# Retro_Lite_CM5_Left_PCB_v1_-_RP2040.net
KiCad netlist of a schematic drawn in EAGLE
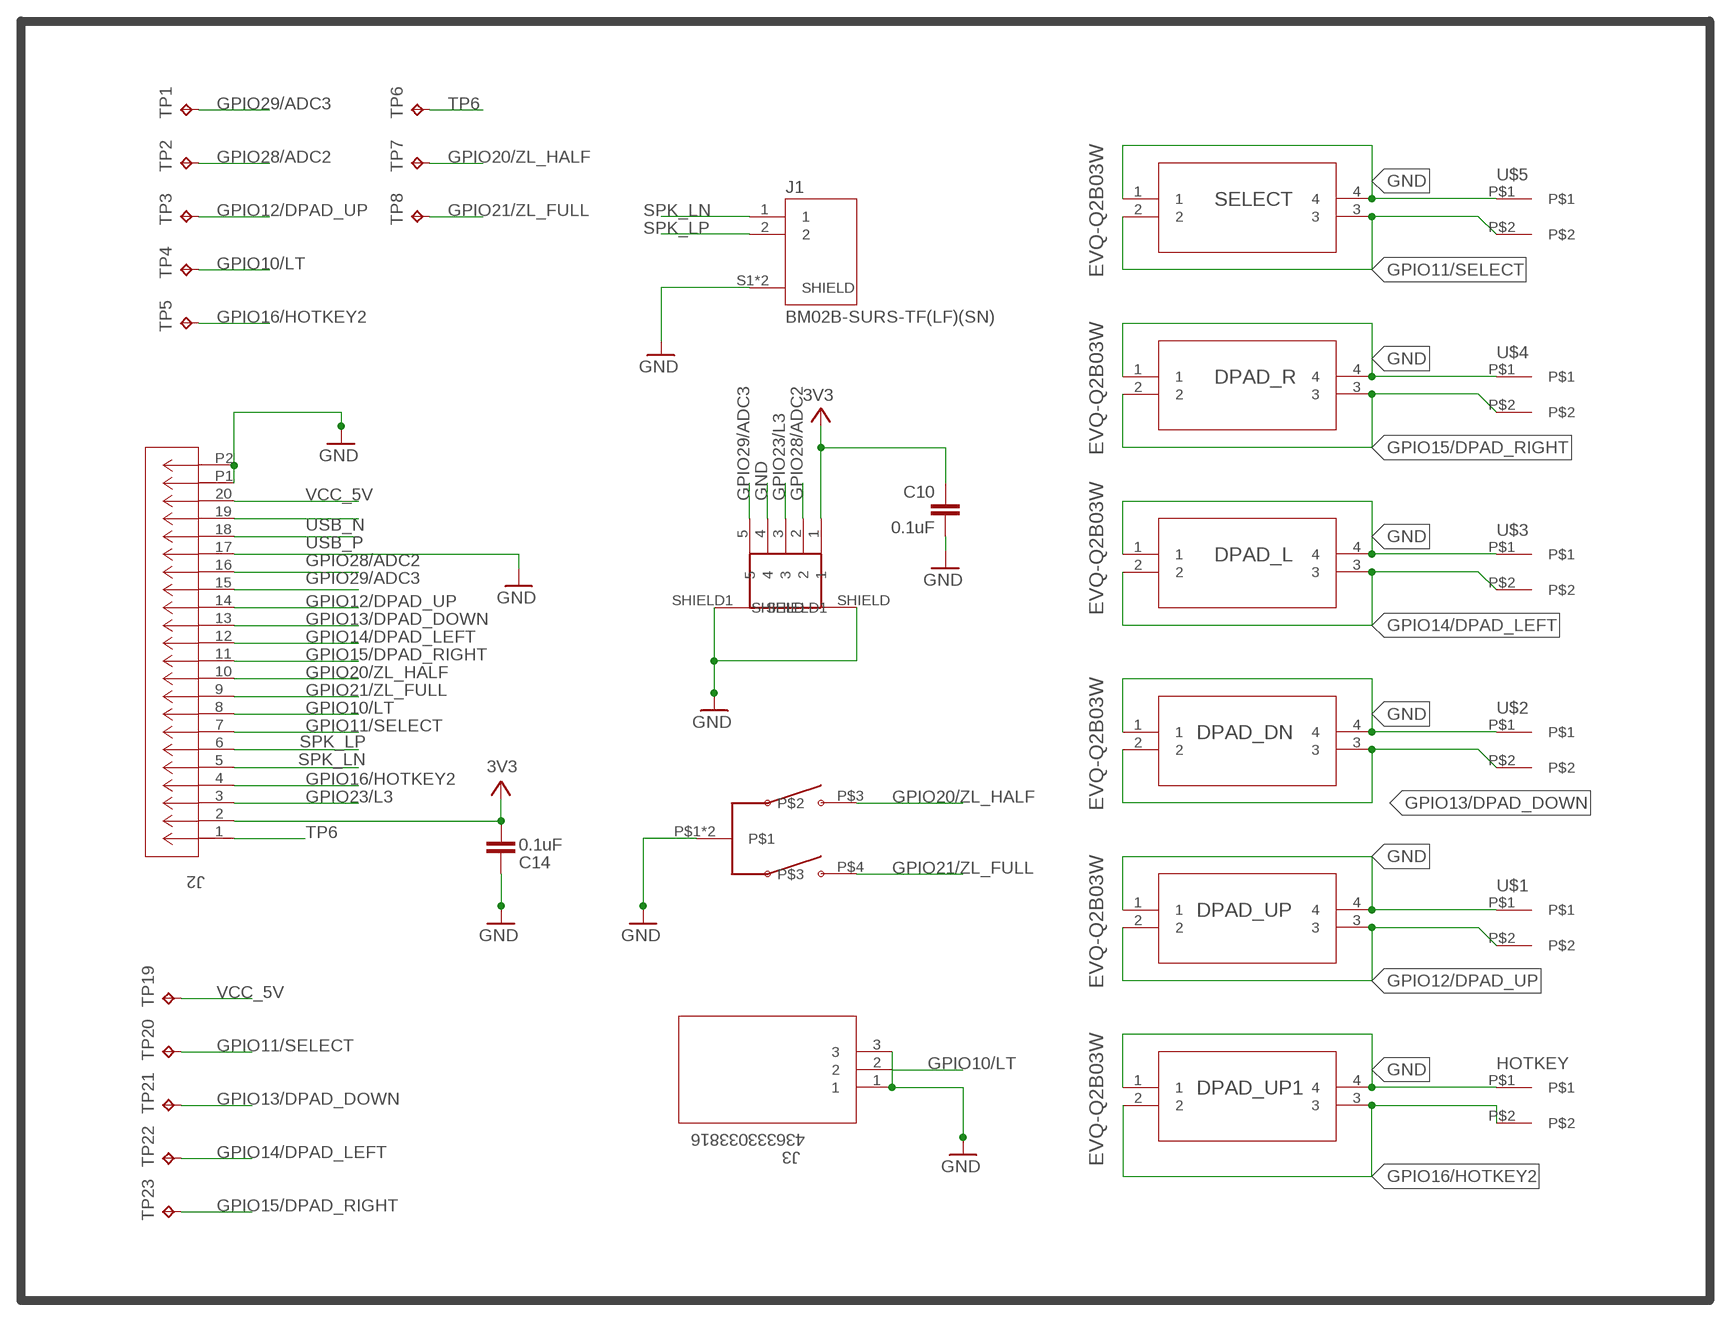
[diagram p0: schematic, sheet 1]

(export (version "E")
  (design (tool "Eeschema 10.0.6"))
  (components
    (comp (ref "C10")
      (value "0.1uF")
      (footprint "eagle-import:C0402")
      (libsource (lib "eagle-import") (part "C-EUC0402-YVELTAL"))
    )
    (comp (ref "C14")
      (value "0.1uF")
      (footprint "eagle-import:C0402")
      (libsource (lib "eagle-import") (part "C-EUC0402-YVELTAL"))
    )
    (comp (ref "DPAD_DN")
      (value "EVQ-Q2B03W")
      (footprint "eagle-import:EVQQ2_3")
      (fields (field (name "MF") "Panasonic Electronic") (field (name "MP") "EVQQ2B03W"))
      (libsource (lib "eagle-import") (part "EVQ-Q2B03W"))
    )
    (comp (ref "DPAD_L")
      (value "EVQ-Q2B03W")
      (footprint "eagle-import:EVQQ2_3")
      (fields (field (name "MF") "Panasonic Electronic") (field (name "MP") "EVQQ2B03W"))
      (libsource (lib "eagle-import") (part "EVQ-Q2B03W"))
    )
    (comp (ref "DPAD_R")
      (value "EVQ-Q2B03W")
      (footprint "eagle-import:EVQQ2_3")
      (fields (field (name "MF") "Panasonic Electronic") (field (name "MP") "EVQQ2B03W"))
      (libsource (lib "eagle-import") (part "EVQ-Q2B03W"))
    )
    (comp (ref "DPAD_UP")
      (value "EVQ-Q2B03W")
      (footprint "eagle-import:EVQQ2_3")
      (fields (field (name "MF") "Panasonic Electronic") (field (name "MP") "EVQQ2B03W"))
      (libsource (lib "eagle-import") (part "EVQ-Q2B03W"))
    )
    (comp (ref "DPAD_UP1")
      (value "EVQ-Q2B03W")
      (footprint "eagle-import:EVQQ2_3")
      (fields (field (name "MF") "Panasonic Electronic") (field (name "MP") "EVQQ2B03W"))
      (libsource (lib "eagle-import") (part "EVQ-Q2B03W"))
    )
    (comp (ref "HOTKEY")
      (value "MEMBRANEBUTTON")
      (footprint "eagle-import:MEMBRANEBUTTON")
      (libsource (lib "eagle-import") (part "MEMBRANEBUTTON"))
    )
    (comp (ref "J1")
      (value "BM02B-SURS-TF(LF)(SN)")
      (footprint "eagle-import:JST_BM02B-SURS-TF(LF)(SN)")
      (fields (field (name "MF") "JST Sales"))
      (libsource (lib "eagle-import") (part "BM02B-SURS-TF(LF)(SN)"))
    )
    (comp (ref "J2")
      (value "5034802000")
      (footprint "eagle-import:CON_5034802000_MOL")
      (fields (field (name "COPYRIGHT") "Copyright (C) 2023 Ultra Librarian. All rights reserved."))
      (libsource (lib "eagle-import") (part "5034802000"))
    )
    (comp (ref "J3")
      (value "436333033816")
      (footprint "eagle-import:CONN3_3033816_WRE")
      (fields (field (name "COPYRIGHT") "Copyright (C) 2023 Ultra Librarian. All rights reserved."))
      (libsource (lib "eagle-import") (part "436333033816"))
    )
    (comp (ref "SELECT")
      (value "EVQ-Q2B03W")
      (footprint "eagle-import:EVQQ2_3")
      (fields (field (name "MF") "Panasonic Electronic") (field (name "MP") "EVQQ2B03W"))
      (libsource (lib "eagle-import") (part "EVQ-Q2B03W"))
    )
    (comp (ref "TP1")
      (value "TPTP07R")
      (footprint "eagle-import:TP07R")
      (libsource (lib "eagle-import") (part "TPTP07R"))
    )
    (comp (ref "TP2")
      (value "TPTP07R")
      (footprint "eagle-import:TP07R")
      (libsource (lib "eagle-import") (part "TPTP07R"))
    )
    (comp (ref "TP3")
      (value "TPTP07R")
      (footprint "eagle-import:TP07R")
      (libsource (lib "eagle-import") (part "TPTP07R"))
    )
    (comp (ref "TP4")
      (value "TPTP07R")
      (footprint "eagle-import:TP07R")
      (libsource (lib "eagle-import") (part "TPTP07R"))
    )
    (comp (ref "TP5")
      (value "TPTP07R")
      (footprint "eagle-import:TP07R")
      (libsource (lib "eagle-import") (part "TPTP07R"))
    )
    (comp (ref "TP6")
      (value "TPTP07R")
      (footprint "eagle-import:TP07R")
      (libsource (lib "eagle-import") (part "TPTP07R"))
    )
    (comp (ref "TP7")
      (value "TPTP07R")
      (footprint "eagle-import:TP07R")
      (libsource (lib "eagle-import") (part "TPTP07R"))
    )
    (comp (ref "TP8")
      (value "TPTP07R")
      (footprint "eagle-import:TP07R")
      (libsource (lib "eagle-import") (part "TPTP07R"))
    )
    (comp (ref "TP19")
      (value "TPTP07R")
      (footprint "eagle-import:TP07R")
      (libsource (lib "eagle-import") (part "TPTP07R"))
    )
    (comp (ref "TP20")
      (value "TPTP07R")
      (footprint "eagle-import:TP07R")
      (libsource (lib "eagle-import") (part "TPTP07R"))
    )
    (comp (ref "TP21")
      (value "TPTP07R")
      (footprint "eagle-import:TP07R")
      (libsource (lib "eagle-import") (part "TPTP07R"))
    )
    (comp (ref "TP22")
      (value "TPTP07R")
      (footprint "eagle-import:TP07R")
      (libsource (lib "eagle-import") (part "TPTP07R"))
    )
    (comp (ref "TP23")
      (value "TPTP07R")
      (footprint "eagle-import:TP07R")
      (libsource (lib "eagle-import") (part "TPTP07R"))
    )
    (comp (ref "U$1")
      (value "MEMBRANEBUTTON")
      (footprint "eagle-import:MEMBRANEBUTTON")
      (libsource (lib "eagle-import") (part "MEMBRANEBUTTON"))
    )
    (comp (ref "U$2")
      (value "MEMBRANEBUTTON")
      (footprint "eagle-import:MEMBRANEBUTTON")
      (libsource (lib "eagle-import") (part "MEMBRANEBUTTON"))
    )
    (comp (ref "U$3")
      (value "MEMBRANEBUTTON")
      (footprint "eagle-import:MEMBRANEBUTTON")
      (libsource (lib "eagle-import") (part "MEMBRANEBUTTON"))
    )
    (comp (ref "U$4")
      (value "MEMBRANEBUTTON")
      (footprint "eagle-import:MEMBRANEBUTTON")
      (libsource (lib "eagle-import") (part "MEMBRANEBUTTON"))
    )
    (comp (ref "U$5")
      (value "MEMBRANEBUTTON")
      (footprint "eagle-import:MEMBRANEBUTTON")
      (libsource (lib "eagle-import") (part "MEMBRANEBUTTON"))
    )
    (comp (ref "U$7")
      (value "SWITCHSTICK_BREAKOUT")
      (footprint "eagle-import:SWITCHSTICK_BREAKOUT")
      (libsource (lib "eagle-import") (part "SWITCHSTICK_BREAKOUT"))
    )
    (comp (ref "U$8")
      (value "TMHF07")
      (footprint "eagle-import:TMHF07")
      (libsource (lib "eagle-import") (part "TMHF07"))
    )
  )
  (nets
    (net (code "1") (name "/GPIO10{slash}LT") (class "Default")
      (node (ref "J2") (pin "8") (pinfunction "8_8") (pintype "passive"))
      (node (ref "J3") (pin "2") (pinfunction "2_2") (pintype "passive"))
      (node (ref "TP4") (pin "TP") (pinfunction "TP_TP") (pintype "input"))
    )
    (net (code "2") (name "/GPIO20{slash}ZL_HALF") (class "Default")
      (node (ref "J2") (pin "10") (pinfunction "10_10") (pintype "passive"))
      (node (ref "TP7") (pin "TP") (pinfunction "TP_TP") (pintype "input"))
      (node (ref "U$8") (pin "P$3") (pinfunction "P$2_P$3") (pintype "bidirectional"))
    )
    (net (code "3") (name "/GPIO21{slash}ZL_FULL") (class "Default")
      (node (ref "J2") (pin "9") (pinfunction "9_9") (pintype "passive"))
      (node (ref "TP8") (pin "TP") (pinfunction "TP_TP") (pintype "input"))
      (node (ref "U$8") (pin "P$4") (pinfunction "P$3_P$4") (pintype "bidirectional"))
    )
    (net (code "4") (name "/GPIO23{slash}L3") (class "Default")
      (node (ref "J2") (pin "3") (pinfunction "3_3") (pintype "passive"))
      (node (ref "U$7") (pin "3") (pinfunction "3_3") (pintype "bidirectional"))
    )
    (net (code "5") (name "/GPIO28{slash}ADC2") (class "Default")
      (node (ref "J2") (pin "16") (pinfunction "16_16") (pintype "passive"))
      (node (ref "TP2") (pin "TP") (pinfunction "TP_TP") (pintype "input"))
      (node (ref "U$7") (pin "2") (pinfunction "2_2") (pintype "bidirectional"))
    )
    (net (code "6") (name "/GPIO29{slash}ADC3") (class "Default")
      (node (ref "J2") (pin "15") (pinfunction "15_15") (pintype "passive"))
      (node (ref "TP1") (pin "TP") (pinfunction "TP_TP") (pintype "input"))
      (node (ref "U$7") (pin "5") (pinfunction "5_5") (pintype "bidirectional"))
    )
    (net (code "7") (name "/SPK_LN") (class "Default")
      (node (ref "J1") (pin "1") (pinfunction "1_1") (pintype "passive"))
      (node (ref "J2") (pin "5") (pinfunction "5_5") (pintype "passive"))
    )
    (net (code "8") (name "/SPK_LP") (class "Default")
      (node (ref "J1") (pin "2") (pinfunction "2_2") (pintype "passive"))
      (node (ref "J2") (pin "6") (pinfunction "6_6") (pintype "passive"))
    )
    (net (code "9") (name "/TP6") (class "Default")
      (node (ref "J2") (pin "1") (pinfunction "1_1") (pintype "passive"))
      (node (ref "TP6") (pin "TP") (pinfunction "TP_TP") (pintype "input"))
    )
    (net (code "10") (name "/USB_N") (class "Default")
      (node (ref "J2") (pin "19") (pinfunction "19_19") (pintype "passive"))
    )
    (net (code "11") (name "/USB_P") (class "Default")
      (node (ref "J2") (pin "18") (pinfunction "18_18") (pintype "passive"))
    )
    (net (code "12") (name "/VCC_5V") (class "Default")
      (node (ref "J2") (pin "20") (pinfunction "20_20") (pintype "passive"))
      (node (ref "TP19") (pin "TP") (pinfunction "TP_TP") (pintype "input"))
    )
    (net (code "13") (name "GND") (class "Default")
      (node (ref "C10") (pin "2") (pinfunction "2_2") (pintype "passive"))
      (node (ref "C14") (pin "1") (pinfunction "1_1") (pintype "passive"))
      (node (ref "DPAD_DN") (pin "1") (pinfunction "1_1") (pintype "passive"))
      (node (ref "DPAD_DN") (pin "4") (pinfunction "4_4") (pintype "passive"))
      (node (ref "DPAD_L") (pin "1") (pinfunction "1_1") (pintype "passive"))
      (node (ref "DPAD_L") (pin "4") (pinfunction "4_4") (pintype "passive"))
      (node (ref "DPAD_R") (pin "1") (pinfunction "1_1") (pintype "passive"))
      (node (ref "DPAD_R") (pin "4") (pinfunction "4_4") (pintype "passive"))
      (node (ref "DPAD_UP") (pin "1") (pinfunction "1_1") (pintype "passive"))
      (node (ref "DPAD_UP") (pin "4") (pinfunction "4_4") (pintype "passive"))
      (node (ref "DPAD_UP1") (pin "1") (pinfunction "1_1") (pintype "passive"))
      (node (ref "DPAD_UP1") (pin "4") (pinfunction "4_4") (pintype "passive"))
      (node (ref "HOTKEY") (pin "P$1") (pinfunction "P$1_P$1") (pintype "bidirectional"))
      (node (ref "J1") (pin "S1") (pinfunction "SHIELD_S1") (pintype "passive"))
      (node (ref "J1") (pin "S2") (pinfunction "SHIELD_S2") (pintype "passive"))
      (node (ref "J2") (pin "17") (pinfunction "17_17") (pintype "passive"))
      (node (ref "J2") (pin "P1") (pinfunction "P1_P1") (pintype "passive"))
      (node (ref "J2") (pin "P2") (pinfunction "P2_P2") (pintype "passive"))
      (node (ref "J3") (pin "1") (pinfunction "1_1") (pintype "passive"))
      (node (ref "J3") (pin "3") (pinfunction "3_3") (pintype "passive"))
      (node (ref "SELECT") (pin "1") (pinfunction "1_1") (pintype "passive"))
      (node (ref "SELECT") (pin "4") (pinfunction "4_4") (pintype "passive"))
      (node (ref "U$1") (pin "P$1") (pinfunction "P$1_P$1") (pintype "bidirectional"))
      (node (ref "U$2") (pin "P$1") (pinfunction "P$1_P$1") (pintype "bidirectional"))
      (node (ref "U$3") (pin "P$1") (pinfunction "P$1_P$1") (pintype "bidirectional"))
      (node (ref "U$4") (pin "P$1") (pinfunction "P$1_P$1") (pintype "bidirectional"))
      (node (ref "U$5") (pin "P$1") (pinfunction "P$1_P$1") (pintype "bidirectional"))
      (node (ref "U$7") (pin "4") (pinfunction "4_4") (pintype "bidirectional"))
      (node (ref "U$7") (pin "SHIELD") (pinfunction "SHIELD_SHIELD") (pintype "bidirectional"))
      (node (ref "U$7") (pin "SHIELD1") (pinfunction "SHIELD1_SHIELD1") (pintype "bidirectional"))
      (node (ref "U$8") (pin "P$1") (pinfunction "P$1_P$1") (pintype "bidirectional"))
      (node (ref "U$8") (pin "P$2") (pinfunction "P$1_P$2") (pintype "bidirectional"))
    )
    (net (code "14") (name "GPIO11{slash}SELECT") (class "Default")
      (node (ref "J2") (pin "7") (pinfunction "7_7") (pintype "passive"))
      (node (ref "SELECT") (pin "2") (pinfunction "2_2") (pintype "passive"))
      (node (ref "SELECT") (pin "3") (pinfunction "3_3") (pintype "passive"))
      (node (ref "TP20") (pin "TP") (pinfunction "TP_TP") (pintype "input"))
      (node (ref "U$5") (pin "P$2") (pinfunction "P$2_P$2") (pintype "bidirectional"))
    )
    (net (code "15") (name "GPIO12{slash}DPAD_UP") (class "Default")
      (node (ref "DPAD_UP") (pin "2") (pinfunction "2_2") (pintype "passive"))
      (node (ref "DPAD_UP") (pin "3") (pinfunction "3_3") (pintype "passive"))
      (node (ref "J2") (pin "14") (pinfunction "14_14") (pintype "passive"))
      (node (ref "TP3") (pin "TP") (pinfunction "TP_TP") (pintype "input"))
      (node (ref "U$1") (pin "P$2") (pinfunction "P$2_P$2") (pintype "bidirectional"))
    )
    (net (code "16") (name "GPIO13{slash}DPAD_DOWN") (class "Default")
      (node (ref "DPAD_DN") (pin "2") (pinfunction "2_2") (pintype "passive"))
      (node (ref "DPAD_DN") (pin "3") (pinfunction "3_3") (pintype "passive"))
      (node (ref "J2") (pin "13") (pinfunction "13_13") (pintype "passive"))
      (node (ref "TP21") (pin "TP") (pinfunction "TP_TP") (pintype "input"))
      (node (ref "U$2") (pin "P$2") (pinfunction "P$2_P$2") (pintype "bidirectional"))
    )
    (net (code "17") (name "GPIO14{slash}DPAD_LEFT") (class "Default")
      (node (ref "DPAD_L") (pin "2") (pinfunction "2_2") (pintype "passive"))
      (node (ref "DPAD_L") (pin "3") (pinfunction "3_3") (pintype "passive"))
      (node (ref "J2") (pin "12") (pinfunction "12_12") (pintype "passive"))
      (node (ref "TP22") (pin "TP") (pinfunction "TP_TP") (pintype "input"))
      (node (ref "U$3") (pin "P$2") (pinfunction "P$2_P$2") (pintype "bidirectional"))
    )
    (net (code "18") (name "GPIO15{slash}DPAD_RIGHT") (class "Default")
      (node (ref "DPAD_R") (pin "2") (pinfunction "2_2") (pintype "passive"))
      (node (ref "DPAD_R") (pin "3") (pinfunction "3_3") (pintype "passive"))
      (node (ref "J2") (pin "11") (pinfunction "11_11") (pintype "passive"))
      (node (ref "TP23") (pin "TP") (pinfunction "TP_TP") (pintype "input"))
      (node (ref "U$4") (pin "P$2") (pinfunction "P$2_P$2") (pintype "bidirectional"))
    )
    (net (code "19") (name "GPIO16{slash}HOTKEY2") (class "Default")
      (node (ref "DPAD_UP1") (pin "2") (pinfunction "2_2") (pintype "passive"))
      (node (ref "DPAD_UP1") (pin "3") (pinfunction "3_3") (pintype "passive"))
      (node (ref "HOTKEY") (pin "P$2") (pinfunction "P$2_P$2") (pintype "bidirectional"))
      (node (ref "J2") (pin "4") (pinfunction "4_4") (pintype "passive"))
      (node (ref "TP5") (pin "TP") (pinfunction "TP_TP") (pintype "input"))
    )
    (net (code "20") (name "VCC") (class "Default")
      (node (ref "C10") (pin "1") (pinfunction "1_1") (pintype "passive"))
      (node (ref "C14") (pin "2") (pinfunction "2_2") (pintype "passive"))
      (node (ref "J2") (pin "2") (pinfunction "2_2") (pintype "passive"))
      (node (ref "U$7") (pin "1") (pinfunction "1_1") (pintype "bidirectional"))
    )
  )
)
